# BlinkyTape_Controller.net
KiCad netlist of a schematic drawn in EAGLE
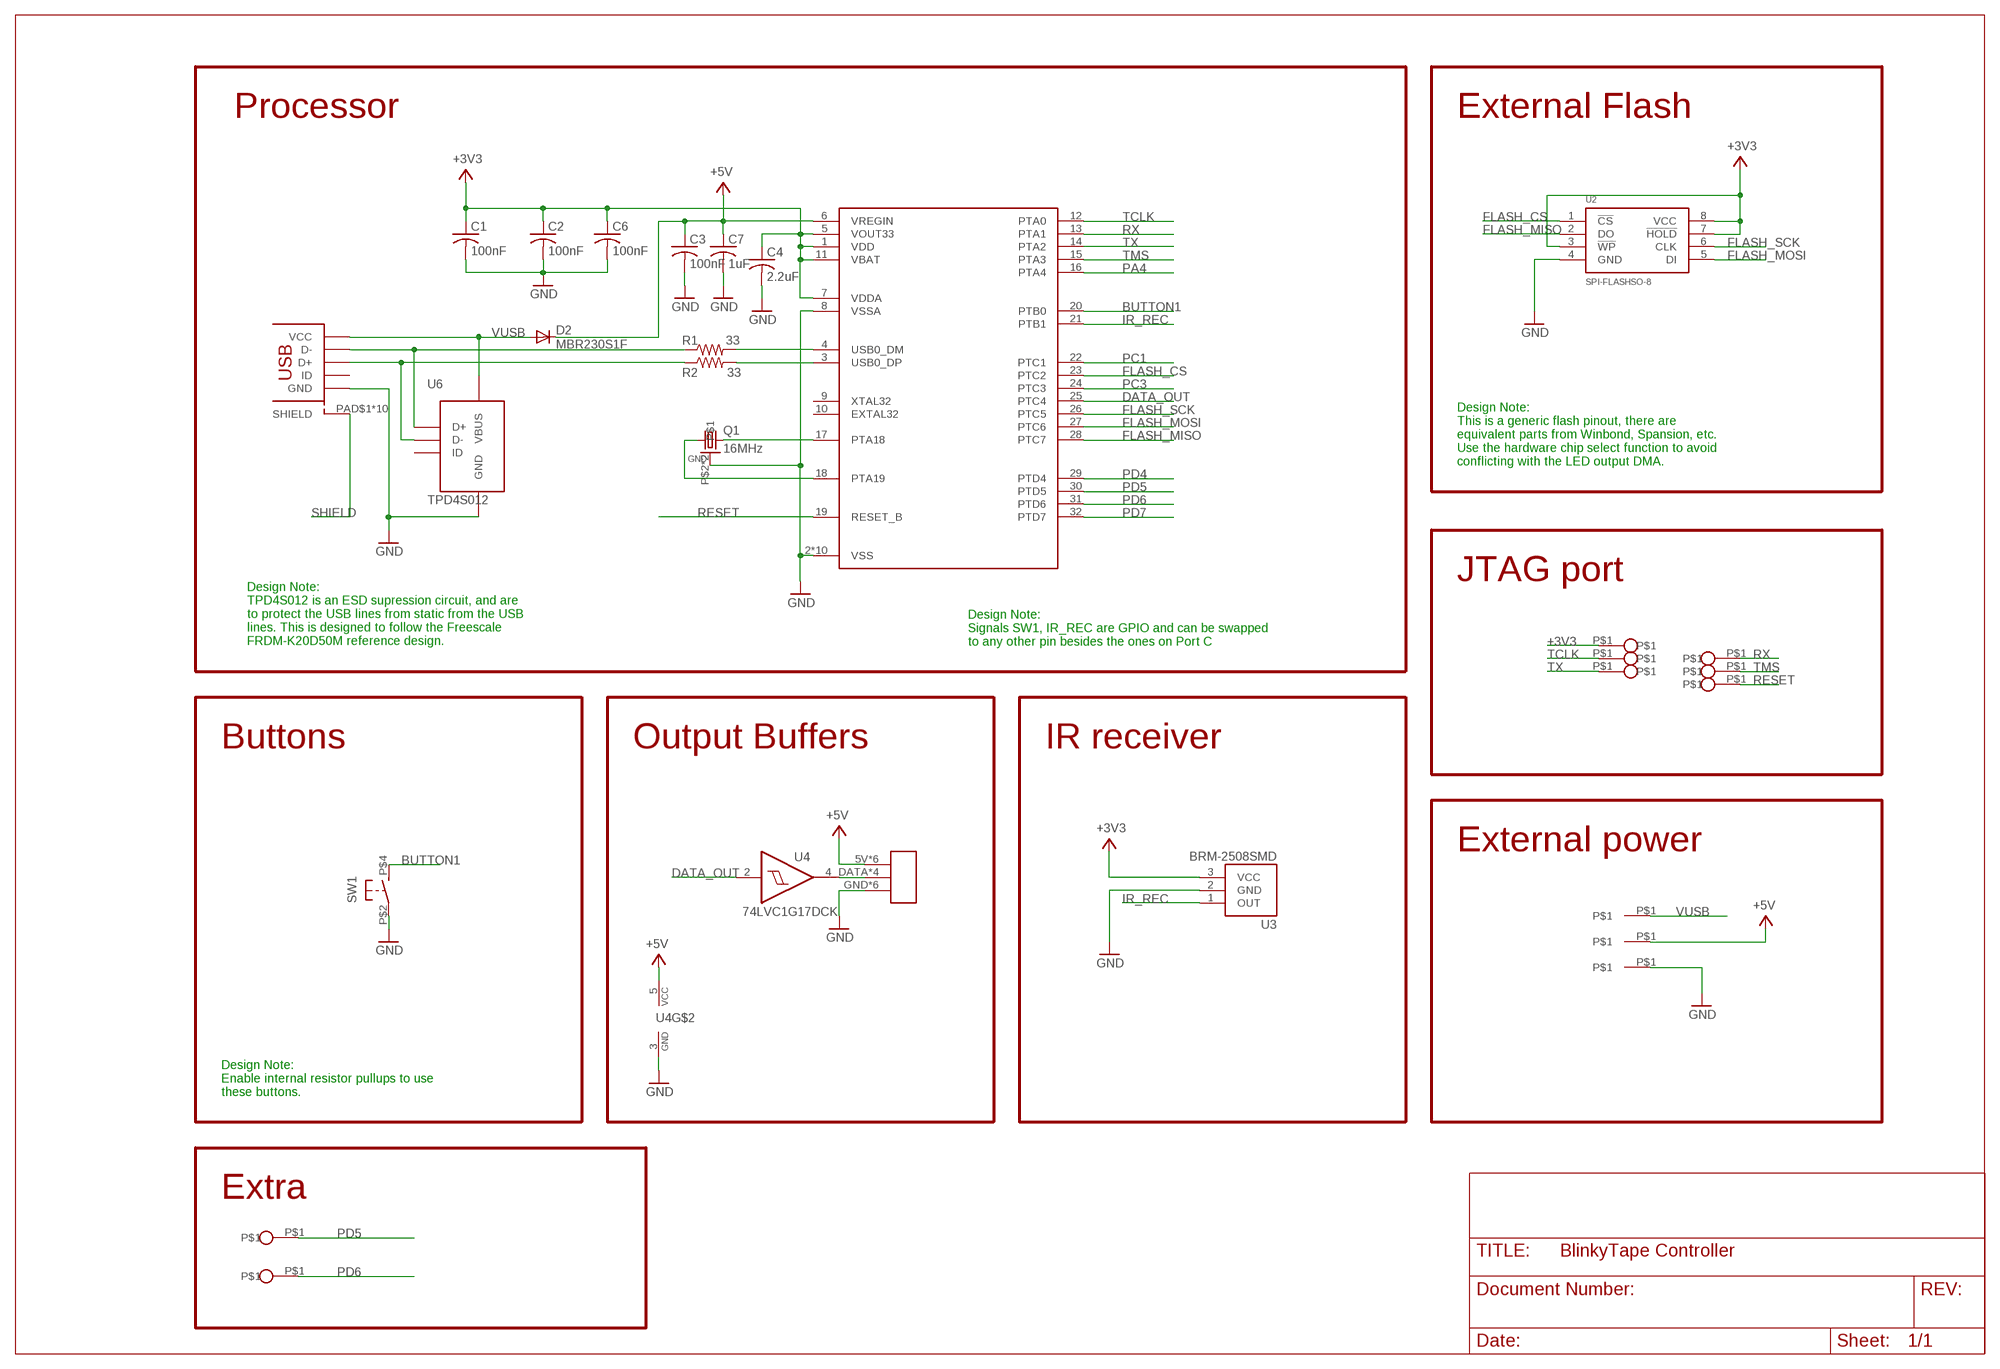
[diagram p0: schematic, sheet 1]

(export (version "E")
  (design (tool "Eeschema 10.0.6"))
  (components
    (comp (ref "C1")
      (value "100nF")
      (footprint "eagle-import:C0402")
      (libsource (lib "eagle-import") (part "C-USC0402"))
    )
    (comp (ref "C2")
      (value "100nF")
      (footprint "eagle-import:C0402")
      (libsource (lib "eagle-import") (part "C-USC0402"))
    )
    (comp (ref "C3")
      (value "100nF")
      (footprint "eagle-import:C0402")
      (libsource (lib "eagle-import") (part "C-USC0402"))
    )
    (comp (ref "C4")
      (value "2.2uF")
      (footprint "eagle-import:C0402")
      (libsource (lib "eagle-import") (part "C-USC0402"))
    )
    (comp (ref "C6")
      (value "100nF")
      (footprint "eagle-import:C0402")
      (libsource (lib "eagle-import") (part "C-USC0402"))
    )
    (comp (ref "C7")
      (value "1uF")
      (footprint "eagle-import:C0603")
      (libsource (lib "eagle-import") (part "C-USC0603"))
    )
    (comp (ref "CON1")
      (value "USB_MICROSMT+THRUHULE")
      (footprint "eagle-import:USB_MICRO_THRUHOLE")
      (libsource (lib "eagle-import") (part "USB_MICROSMT+THRUHULE"))
    )
    (comp (ref "D2")
      (value "MBR230S1F")
      (footprint "eagle-import:SOD123")
      (fields (field (name "MPN") "B340A-13-F"))
      (libsource (lib "eagle-import") (part "SPARKFUN-DISCRETESEMI_DIODESOD123SOD123"))
    )
    (comp (ref "Q1")
      (value "16MHz")
      (footprint "eagle-import:CRSYTAL_2520")
      (libsource (lib "eagle-import") (part "CRYSTAL_4PAD2520"))
    )
    (comp (ref "R1")
      (value "33")
      (footprint "eagle-import:R0402")
      (libsource (lib "eagle-import") (part "R-US_R0402"))
    )
    (comp (ref "R2")
      (value "33")
      (footprint "eagle-import:R0402")
      (libsource (lib "eagle-import") (part "R-US_R0402"))
    )
    (comp (ref "RECT_PAD1")
      (value "TEST_PAD_SMTRECT_PAD")
      (footprint "eagle-import:TEST_PAD_SMT")
      (libsource (lib "eagle-import") (part "TEST_PAD_SMTRECT_PAD"))
    )
    (comp (ref "RECT_PAD2")
      (value "TEST_PAD_SMTRECT_PAD")
      (footprint "eagle-import:TEST_PAD_SMT")
      (libsource (lib "eagle-import") (part "TEST_PAD_SMTRECT_PAD"))
    )
    (comp (ref "RECT_PAD3")
      (value "TEST_PAD_SMTRECT_PAD")
      (footprint "eagle-import:TEST_PAD_SMT")
      (libsource (lib "eagle-import") (part "TEST_PAD_SMTRECT_PAD"))
    )
    (comp (ref "SW1")
      (value "BUTTON_MOMENTARY")
      (footprint "eagle-import:BUTTON_MOMENTARY_KMR211G")
      (libsource (lib "eagle-import") (part "BUTTON_MOMENTARY"))
    )
    (comp (ref "U$1")
      (value "WS2812B_CONNECTOR")
      (footprint "eagle-import:WS2812B_CONNECTOR_COMBINED")
      (libsource (lib "eagle-import") (part "WS2812B_CONNECTOR"))
    )
    (comp (ref "U$2")
      (value "POGO_PINSMD")
      (footprint "eagle-import:POGO_PIN_SMD")
      (libsource (lib "eagle-import") (part "POGO_PINSMD"))
    )
    (comp (ref "U$3")
      (value "POGO_PINSMD")
      (footprint "eagle-import:POGO_PIN_SMD")
      (libsource (lib "eagle-import") (part "POGO_PINSMD"))
    )
    (comp (ref "U$4")
      (value "POGO_PINSMD")
      (footprint "eagle-import:POGO_PIN_SMD")
      (libsource (lib "eagle-import") (part "POGO_PINSMD"))
    )
    (comp (ref "U$5")
      (value "POGO_PINSMD")
      (footprint "eagle-import:POGO_PIN_SMD")
      (libsource (lib "eagle-import") (part "POGO_PINSMD"))
    )
    (comp (ref "U$6")
      (value "POGO_PINSMD")
      (footprint "eagle-import:POGO_PIN_SMD")
      (libsource (lib "eagle-import") (part "POGO_PINSMD"))
    )
    (comp (ref "U$7")
      (value "POGO_PINSMD")
      (footprint "eagle-import:POGO_PIN_SMD")
      (libsource (lib "eagle-import") (part "POGO_PINSMD"))
    )
    (comp (ref "U$8")
      (value "POGO_PINSMD")
      (footprint "eagle-import:POGO_PIN_SMD")
      (libsource (lib "eagle-import") (part "POGO_PINSMD"))
    )
    (comp (ref "U$9")
      (value "POGO_PINSMD")
      (footprint "eagle-import:POGO_PIN_SMD")
      (libsource (lib "eagle-import") (part "POGO_PINSMD"))
    )
    (comp (ref "U1")
      (value "MK20D--VFM5")
      (footprint "eagle-import:QFN32_5X5_LONGLEADS")
      (libsource (lib "eagle-import") (part "MK20D--VFM5"))
    )
    (comp (ref "U2")
      (value "SPI-FLASHSO-8")
      (footprint "eagle-import:SO08")
      (libsource (lib "eagle-import") (part "SPI-FLASHSO-8"))
    )
    (comp (ref "U3")
      (value "BRM-2508SMD")
      (footprint "eagle-import:BRM-2508_SMD")
      (libsource (lib "eagle-import") (part "BRM-2508SMD"))
    )
    (comp (ref "U4")
      (value "74LVC1G17DCK")
      (footprint "eagle-import:SC70-5")
      (libsource (lib "eagle-import") (part "741G17DCKLVC"))
    )
    (comp (ref "U6")
      (value "TPD4S012")
      (footprint "eagle-import:R-PUSON-N6")
      (libsource (lib "eagle-import") (part "TPD4S012"))
    )
  )
  (nets
    (net (code "1") (name "+3V3") (class "Default")
      (node (ref "C1") (pin "1") (pinfunction "1_1") (pintype "passive"))
      (node (ref "C2") (pin "1") (pinfunction "1_1") (pintype "passive"))
      (node (ref "C4") (pin "1") (pinfunction "1_1") (pintype "passive"))
      (node (ref "C6") (pin "1") (pinfunction "1_1") (pintype "passive"))
      (node (ref "U$2") (pin "P$1") (pinfunction "P$1_P$1") (pintype "bidirectional"))
      (node (ref "U1") (pin "1") (pinfunction "VDD_1") (pintype "bidirectional"))
      (node (ref "U1") (pin "11") (pinfunction "VBAT_11") (pintype "bidirectional"))
      (node (ref "U1") (pin "5") (pinfunction "VOUT33_5") (pintype "bidirectional"))
      (node (ref "U1") (pin "7") (pinfunction "VDDA_7") (pintype "bidirectional"))
      (node (ref "U2") (pin "3") (pinfunction "~{WP}_3") (pintype "bidirectional"))
      (node (ref "U2") (pin "7") (pinfunction "~{HOLD}_7") (pintype "bidirectional"))
      (node (ref "U2") (pin "8") (pinfunction "VCC_8") (pintype "bidirectional"))
      (node (ref "U3") (pin "3") (pinfunction "VCC_3") (pintype "bidirectional"))
    )
    (net (code "2") (name "+5V") (class "Default")
      (node (ref "C3") (pin "1") (pinfunction "1_1") (pintype "passive"))
      (node (ref "C7") (pin "1") (pinfunction "1_1") (pintype "passive"))
      (node (ref "D2") (pin "C") (pinfunction "C_C") (pintype "passive"))
      (node (ref "RECT_PAD2") (pin "P$1") (pinfunction "P$1_P$1") (pintype "bidirectional"))
      (node (ref "U$1") (pin "5V") (pinfunction "5V_5V") (pintype "bidirectional"))
      (node (ref "U$1") (pin "5V1") (pinfunction "5V_5V1") (pintype "bidirectional"))
      (node (ref "U$1") (pin "5V2") (pinfunction "5V_5V2") (pintype "bidirectional"))
      (node (ref "U$1") (pin "5V_1") (pinfunction "5V_5V_1") (pintype "bidirectional"))
      (node (ref "U$1") (pin "5V_2") (pinfunction "5V_5V_2") (pintype "bidirectional"))
      (node (ref "U$1") (pin "5V_3") (pinfunction "5V_5V_3") (pintype "bidirectional"))
      (node (ref "U1") (pin "6") (pinfunction "VREGIN_6") (pintype "bidirectional"))
      (node (ref "U4") (pin "5") (pinfunction "VCC_5") (pintype "power_in"))
    )
    (net (code "3") (name "/BUTTON1") (class "Default")
      (node (ref "SW1") (pin "P$4") (pinfunction "S_P$4") (pintype "passive"))
      (node (ref "U1") (pin "20") (pinfunction "PTB0_20") (pintype "bidirectional"))
    )
    (net (code "4") (name "/DATA_OUT") (class "Default")
      (node (ref "U1") (pin "25") (pinfunction "PTC4_25") (pintype "bidirectional"))
      (node (ref "U4") (pin "2") (pinfunction "I_2") (pintype "input"))
    )
    (net (code "5") (name "/FLASH_CS") (class "Default")
      (node (ref "U1") (pin "23") (pinfunction "PTC2_23") (pintype "bidirectional"))
      (node (ref "U2") (pin "1") (pinfunction "~{CS}_1") (pintype "bidirectional"))
    )
    (net (code "6") (name "/FLASH_MISO") (class "Default")
      (node (ref "U1") (pin "28") (pinfunction "PTC7_28") (pintype "bidirectional"))
      (node (ref "U2") (pin "2") (pinfunction "DO_2") (pintype "bidirectional"))
    )
    (net (code "7") (name "/FLASH_MOSI") (class "Default")
      (node (ref "U1") (pin "27") (pinfunction "PTC6_27") (pintype "bidirectional"))
      (node (ref "U2") (pin "5") (pinfunction "DI_5") (pintype "bidirectional"))
    )
    (net (code "8") (name "/FLASH_SCK") (class "Default")
      (node (ref "U1") (pin "26") (pinfunction "PTC5_26") (pintype "bidirectional"))
      (node (ref "U2") (pin "6") (pinfunction "CLK_6") (pintype "bidirectional"))
    )
    (net (code "9") (name "/IR_REC") (class "Default")
      (node (ref "U1") (pin "21") (pinfunction "PTB1_21") (pintype "bidirectional"))
      (node (ref "U3") (pin "1") (pinfunction "OUT_1") (pintype "bidirectional"))
    )
    (net (code "10") (name "/PA4") (class "Default")
      (node (ref "U1") (pin "16") (pinfunction "PTA4_16") (pintype "bidirectional"))
    )
    (net (code "11") (name "/PC1") (class "Default")
      (node (ref "U1") (pin "22") (pinfunction "PTC1_22") (pintype "bidirectional"))
    )
    (net (code "12") (name "/PC3") (class "Default")
      (node (ref "U1") (pin "24") (pinfunction "PTC3_24") (pintype "bidirectional"))
    )
    (net (code "13") (name "/PD4") (class "Default")
      (node (ref "U1") (pin "29") (pinfunction "PTD4_29") (pintype "bidirectional"))
    )
    (net (code "14") (name "/PD5") (class "Default")
      (node (ref "U$5") (pin "P$1") (pinfunction "P$1_P$1") (pintype "bidirectional"))
      (node (ref "U1") (pin "30") (pinfunction "PTD5_30") (pintype "bidirectional"))
    )
    (net (code "15") (name "/PD6") (class "Default")
      (node (ref "U$9") (pin "P$1") (pinfunction "P$1_P$1") (pintype "bidirectional"))
      (node (ref "U1") (pin "31") (pinfunction "PTD6_31") (pintype "bidirectional"))
    )
    (net (code "16") (name "/PD7") (class "Default")
      (node (ref "U1") (pin "32") (pinfunction "PTD7_32") (pintype "bidirectional"))
    )
    (net (code "17") (name "/RESET") (class "Default")
      (node (ref "U$8") (pin "P$1") (pinfunction "P$1_P$1") (pintype "bidirectional"))
      (node (ref "U1") (pin "19") (pinfunction "RESET_B_19") (pintype "bidirectional"))
    )
    (net (code "18") (name "/RX") (class "Default")
      (node (ref "U$6") (pin "P$1") (pinfunction "P$1_P$1") (pintype "bidirectional"))
      (node (ref "U1") (pin "13") (pinfunction "PTA1_13") (pintype "bidirectional"))
    )
    (net (code "19") (name "/SHIELD") (class "Default")
      (node (ref "CON1") (pin "PAD$1") (pinfunction "SHIELD_PAD$1") (pintype "bidirectional"))
      (node (ref "CON1") (pin "PAD$10") (pinfunction "SHIELD_PAD$10") (pintype "bidirectional"))
      (node (ref "CON1") (pin "PAD$2") (pinfunction "SHIELD_PAD$2") (pintype "bidirectional"))
      (node (ref "CON1") (pin "PAD$3") (pinfunction "SHIELD_PAD$3") (pintype "bidirectional"))
      (node (ref "CON1") (pin "PAD$4") (pinfunction "SHIELD_PAD$4") (pintype "bidirectional"))
      (node (ref "CON1") (pin "PAD$5") (pinfunction "SHIELD_PAD$5") (pintype "bidirectional"))
      (node (ref "CON1") (pin "PAD$6") (pinfunction "SHIELD_PAD$6") (pintype "bidirectional"))
      (node (ref "CON1") (pin "PAD$7") (pinfunction "SHIELD_PAD$7") (pintype "bidirectional"))
      (node (ref "CON1") (pin "PAD$8") (pinfunction "SHIELD_PAD$8") (pintype "bidirectional"))
      (node (ref "CON1") (pin "PAD$9") (pinfunction "SHIELD_PAD$9") (pintype "bidirectional"))
    )
    (net (code "20") (name "/TCLK") (class "Default")
      (node (ref "U$3") (pin "P$1") (pinfunction "P$1_P$1") (pintype "bidirectional"))
      (node (ref "U1") (pin "12") (pinfunction "PTA0_12") (pintype "bidirectional"))
    )
    (net (code "21") (name "/TMS") (class "Default")
      (node (ref "U$7") (pin "P$1") (pinfunction "P$1_P$1") (pintype "bidirectional"))
      (node (ref "U1") (pin "15") (pinfunction "PTA3_15") (pintype "bidirectional"))
    )
    (net (code "22") (name "/TX") (class "Default")
      (node (ref "U$4") (pin "P$1") (pinfunction "P$1_P$1") (pintype "bidirectional"))
      (node (ref "U1") (pin "14") (pinfunction "PTA2_14") (pintype "bidirectional"))
    )
    (net (code "23") (name "/VUSB") (class "Default")
      (node (ref "CON1") (pin "PIN$1") (pinfunction "VCC_PIN$1") (pintype "bidirectional"))
      (node (ref "D2") (pin "A") (pinfunction "A_A") (pintype "passive"))
      (node (ref "RECT_PAD1") (pin "P$1") (pinfunction "P$1_P$1") (pintype "bidirectional"))
      (node (ref "U6") (pin "P$6") (pinfunction "VBUS_P$6") (pintype "bidirectional"))
    )
    (net (code "24") (name "GND") (class "Default")
      (node (ref "C1") (pin "2") (pinfunction "2_2") (pintype "passive"))
      (node (ref "C2") (pin "2") (pinfunction "2_2") (pintype "passive"))
      (node (ref "C3") (pin "2") (pinfunction "2_2") (pintype "passive"))
      (node (ref "C4") (pin "2") (pinfunction "2_2") (pintype "passive"))
      (node (ref "C6") (pin "2") (pinfunction "2_2") (pintype "passive"))
      (node (ref "C7") (pin "2") (pinfunction "2_2") (pintype "passive"))
      (node (ref "CON1") (pin "PIN$5") (pinfunction "GND_PIN$5") (pintype "bidirectional"))
      (node (ref "Q1") (pin "P$2") (pinfunction "P$1_P$2") (pintype "bidirectional"))
      (node (ref "Q1") (pin "P$4") (pinfunction "P$1_P$4") (pintype "bidirectional"))
      (node (ref "RECT_PAD3") (pin "P$1") (pinfunction "P$1_P$1") (pintype "bidirectional"))
      (node (ref "SW1") (pin "P$2") (pinfunction "P_P$2") (pintype "passive"))
      (node (ref "U$1") (pin "GND") (pinfunction "GND_GND") (pintype "bidirectional"))
      (node (ref "U$1") (pin "GND1") (pinfunction "GND_GND1") (pintype "bidirectional"))
      (node (ref "U$1") (pin "GND_1") (pinfunction "GND_GND_1") (pintype "bidirectional"))
      (node (ref "U$1") (pin "GND_2") (pinfunction "GND_GND_2") (pintype "bidirectional"))
      (node (ref "U$1") (pin "GND_3") (pinfunction "GND_GND_3") (pintype "bidirectional"))
      (node (ref "U$1") (pin "GND_4") (pinfunction "GND_GND_4") (pintype "bidirectional"))
      (node (ref "U1") (pin "2") (pinfunction "VSS_2") (pintype "bidirectional"))
      (node (ref "U1") (pin "8") (pinfunction "VSSA_8") (pintype "bidirectional"))
      (node (ref "U1") (pin "PAD@1") (pinfunction "VSS_PAD@1") (pintype "bidirectional"))
      (node (ref "U1") (pin "PAD@10") (pinfunction "VSS_PAD@10") (pintype "bidirectional"))
      (node (ref "U1") (pin "PAD@11") (pinfunction "VSS_PAD@11") (pintype "bidirectional"))
      (node (ref "U1") (pin "PAD@2") (pinfunction "VSS_PAD@2") (pintype "bidirectional"))
      (node (ref "U1") (pin "PAD@3") (pinfunction "VSS_PAD@3") (pintype "bidirectional"))
      (node (ref "U1") (pin "PAD@4") (pinfunction "VSS_PAD@4") (pintype "bidirectional"))
      (node (ref "U1") (pin "PAD@5") (pinfunction "VSS_PAD@5") (pintype "bidirectional"))
      (node (ref "U1") (pin "PAD@6") (pinfunction "VSS_PAD@6") (pintype "bidirectional"))
      (node (ref "U1") (pin "PAD@9") (pinfunction "VSS_PAD@9") (pintype "bidirectional"))
      (node (ref "U2") (pin "4") (pinfunction "GND_4") (pintype "bidirectional"))
      (node (ref "U3") (pin "2") (pinfunction "GND_2") (pintype "bidirectional"))
      (node (ref "U4") (pin "3") (pinfunction "GND_3") (pintype "power_in"))
      (node (ref "U6") (pin "P$4") (pinfunction "GND_P$4") (pintype "bidirectional"))
    )
    (net (code "25") (name "Net-(CON1-D+)") (class "Default")
      (node (ref "CON1") (pin "PIN$3") (pinfunction "D+_PIN$3") (pintype "bidirectional"))
      (node (ref "R2") (pin "1") (pinfunction "1_1") (pintype "passive"))
      (node (ref "U6") (pin "P$2") (pinfunction "D-_P$2") (pintype "bidirectional"))
    )
    (net (code "26") (name "Net-(CON1-D-)") (class "Default")
      (node (ref "CON1") (pin "PIN$2") (pinfunction "D-_PIN$2") (pintype "bidirectional"))
      (node (ref "R1") (pin "1") (pinfunction "1_1") (pintype "passive"))
      (node (ref "U6") (pin "P$1") (pinfunction "D+_P$1") (pintype "bidirectional"))
    )
    (net (code "27") (name "Net-(Q1-1)") (class "Default")
      (node (ref "Q1") (pin "P$1") (pinfunction "1_P$1") (pintype "passive"))
      (node (ref "U1") (pin "18") (pinfunction "PTA19_18") (pintype "bidirectional"))
    )
    (net (code "28") (name "Net-(Q1-2)") (class "Default")
      (node (ref "Q1") (pin "P$3") (pinfunction "2_P$3") (pintype "passive"))
      (node (ref "U1") (pin "17") (pinfunction "PTA18_17") (pintype "bidirectional"))
    )
    (net (code "29") (name "Net-(U1-USB0_DM)") (class "Default")
      (node (ref "R1") (pin "2") (pinfunction "2_2") (pintype "passive"))
      (node (ref "U1") (pin "4") (pinfunction "USB0_DM_4") (pintype "bidirectional"))
    )
    (net (code "30") (name "Net-(U1-USB0_DP)") (class "Default")
      (node (ref "R2") (pin "2") (pinfunction "2_2") (pintype "passive"))
      (node (ref "U1") (pin "3") (pinfunction "USB0_DP_3") (pintype "bidirectional"))
    )
    (net (code "31") (name "Net-(U4A-O)") (class "Default")
      (node (ref "U$1") (pin "DATA") (pinfunction "DATA_DATA") (pintype "bidirectional"))
      (node (ref "U$1") (pin "DATA1") (pinfunction "DATA_DATA1") (pintype "bidirectional"))
      (node (ref "U$1") (pin "DATA_1") (pinfunction "DATA_DATA_1") (pintype "bidirectional"))
      (node (ref "U$1") (pin "DATA_2") (pinfunction "DATA_DATA_2") (pintype "bidirectional"))
      (node (ref "U4") (pin "4") (pinfunction "O_4") (pintype "output"))
    )
    (net (code "32") (name "unconnected-(CON1-ID-PadPIN$4)") (class "Default")
      (node (ref "CON1") (pin "PIN$4") (pinfunction "ID_PIN$4") (pintype "bidirectional"))
    )
    (net (code "33") (name "unconnected-(U1-EXTAL32-Pad10)") (class "Default")
      (node (ref "U1") (pin "10") (pinfunction "EXTAL32_10") (pintype "bidirectional"))
    )
    (net (code "34") (name "unconnected-(U1-XTAL32-Pad9)") (class "Default")
      (node (ref "U1") (pin "9") (pinfunction "XTAL32_9") (pintype "bidirectional"))
    )
    (net (code "35") (name "unconnected-(U6-ID-PadP$3)") (class "Default")
      (node (ref "U6") (pin "P$3") (pinfunction "ID_P$3") (pintype "bidirectional"))
    )
  )
)
